# Board1.net
KiCad netlist of a schematic drawn in EAGLE
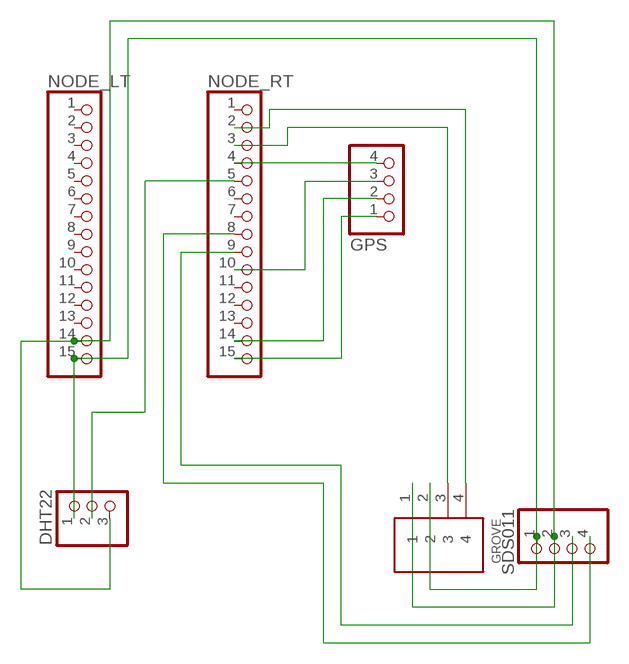
[diagram p0: schematic, sheet 1]

(export (version "E")
  (design (tool "Eeschema 10.0.6"))
  (components
    (comp (ref "DHT22")
      (value "PINHD-1X3")
      (footprint "eagle-import:1X03")
      (libsource (lib "eagle-import") (part "PINHD-1X3"))
    )
    (comp (ref "GPS")
      (value "PINHD-1X4")
      (footprint "eagle-import:1X04")
      (libsource (lib "eagle-import") (part "PINHD-1X4"))
    )
    (comp (ref "GROVE")
      (value "4PIN")
      (footprint "eagle-import:B4B-PH-K-S")
      (libsource (lib "eagle-import") (part "4PIN"))
    )
    (comp (ref "NODE_LT")
      (value "PINHD-1X15")
      (footprint "eagle-import:1X15")
      (libsource (lib "eagle-import") (part "PINHD-1X15"))
    )
    (comp (ref "NODE_RT")
      (value "PINHD-1X15")
      (footprint "eagle-import:1X15")
      (libsource (lib "eagle-import") (part "PINHD-1X15"))
    )
    (comp (ref "SDS011")
      (value "PINHD-1X4")
      (footprint "eagle-import:1X04")
      (libsource (lib "eagle-import") (part "PINHD-1X4"))
    )
  )
  (nets
    (net (code "1") (name "Net-(DHT22-Pad1)") (class "Default")
      (node (ref "DHT22") (pin "1") (pinfunction "1_1") (pintype "passive"))
      (node (ref "GROVE") (pin "2") (pinfunction "2_2") (pintype "bidirectional"))
      (node (ref "NODE_LT") (pin "15") (pinfunction "15_15") (pintype "passive"))
      (node (ref "SDS011") (pin "1") (pinfunction "1_1") (pintype "passive"))
    )
    (net (code "2") (name "Net-(DHT22-Pad2)") (class "Default")
      (node (ref "DHT22") (pin "2") (pinfunction "2_2") (pintype "passive"))
      (node (ref "NODE_RT") (pin "5") (pinfunction "5_5") (pintype "passive"))
    )
    (net (code "3") (name "Net-(DHT22-Pad3)") (class "Default")
      (node (ref "DHT22") (pin "3") (pinfunction "3_3") (pintype "passive"))
      (node (ref "GROVE") (pin "1") (pinfunction "1_1") (pintype "bidirectional"))
      (node (ref "NODE_LT") (pin "14") (pinfunction "14_14") (pintype "passive"))
      (node (ref "SDS011") (pin "2") (pinfunction "2_2") (pintype "passive"))
    )
    (net (code "4") (name "Net-(GPS-Pad1)") (class "Default")
      (node (ref "GPS") (pin "1") (pinfunction "1_1") (pintype "passive"))
      (node (ref "NODE_RT") (pin "15") (pinfunction "15_15") (pintype "passive"))
    )
    (net (code "5") (name "Net-(GPS-Pad2)") (class "Default")
      (node (ref "GPS") (pin "2") (pinfunction "2_2") (pintype "passive"))
      (node (ref "NODE_RT") (pin "14") (pinfunction "14_14") (pintype "passive"))
    )
    (net (code "6") (name "Net-(GPS-Pad3)") (class "Default")
      (node (ref "GPS") (pin "3") (pinfunction "3_3") (pintype "passive"))
      (node (ref "NODE_RT") (pin "10") (pinfunction "10_10") (pintype "passive"))
    )
    (net (code "7") (name "Net-(GPS-Pad4)") (class "Default")
      (node (ref "GPS") (pin "4") (pinfunction "4_4") (pintype "passive"))
      (node (ref "NODE_RT") (pin "4") (pinfunction "4_4") (pintype "passive"))
    )
    (net (code "8") (name "Net-(GROVE-Pad3)") (class "Default")
      (node (ref "GROVE") (pin "3") (pinfunction "3_3") (pintype "bidirectional"))
      (node (ref "NODE_RT") (pin "3") (pinfunction "3_3") (pintype "passive"))
    )
    (net (code "9") (name "Net-(GROVE-Pad4)") (class "Default")
      (node (ref "GROVE") (pin "4") (pinfunction "4_4") (pintype "bidirectional"))
      (node (ref "NODE_RT") (pin "2") (pinfunction "2_2") (pintype "passive"))
    )
    (net (code "10") (name "Net-(NODE_RT-Pad8)") (class "Default")
      (node (ref "NODE_RT") (pin "8") (pinfunction "8_8") (pintype "passive"))
      (node (ref "SDS011") (pin "4") (pinfunction "4_4") (pintype "passive"))
    )
    (net (code "11") (name "Net-(NODE_RT-Pad9)") (class "Default")
      (node (ref "NODE_RT") (pin "9") (pinfunction "9_9") (pintype "passive"))
      (node (ref "SDS011") (pin "3") (pinfunction "3_3") (pintype "passive"))
    )
    (net (code "12") (name "unconnected-(NODE_LT-Pad1)") (class "Default")
      (node (ref "NODE_LT") (pin "1") (pinfunction "1_1") (pintype "passive"))
    )
    (net (code "13") (name "unconnected-(NODE_LT-Pad2)") (class "Default")
      (node (ref "NODE_LT") (pin "2") (pinfunction "2_2") (pintype "passive"))
    )
    (net (code "14") (name "unconnected-(NODE_LT-Pad3)") (class "Default")
      (node (ref "NODE_LT") (pin "3") (pinfunction "3_3") (pintype "passive"))
    )
    (net (code "15") (name "unconnected-(NODE_LT-Pad4)") (class "Default")
      (node (ref "NODE_LT") (pin "4") (pinfunction "4_4") (pintype "passive"))
    )
    (net (code "16") (name "unconnected-(NODE_LT-Pad5)") (class "Default")
      (node (ref "NODE_LT") (pin "5") (pinfunction "5_5") (pintype "passive"))
    )
    (net (code "17") (name "unconnected-(NODE_LT-Pad6)") (class "Default")
      (node (ref "NODE_LT") (pin "6") (pinfunction "6_6") (pintype "passive"))
    )
    (net (code "18") (name "unconnected-(NODE_LT-Pad7)") (class "Default")
      (node (ref "NODE_LT") (pin "7") (pinfunction "7_7") (pintype "passive"))
    )
    (net (code "19") (name "unconnected-(NODE_LT-Pad8)") (class "Default")
      (node (ref "NODE_LT") (pin "8") (pinfunction "8_8") (pintype "passive"))
    )
    (net (code "20") (name "unconnected-(NODE_LT-Pad9)") (class "Default")
      (node (ref "NODE_LT") (pin "9") (pinfunction "9_9") (pintype "passive"))
    )
    (net (code "21") (name "unconnected-(NODE_LT-Pad10)") (class "Default")
      (node (ref "NODE_LT") (pin "10") (pinfunction "10_10") (pintype "passive"))
    )
    (net (code "22") (name "unconnected-(NODE_LT-Pad11)") (class "Default")
      (node (ref "NODE_LT") (pin "11") (pinfunction "11_11") (pintype "passive"))
    )
    (net (code "23") (name "unconnected-(NODE_LT-Pad12)") (class "Default")
      (node (ref "NODE_LT") (pin "12") (pinfunction "12_12") (pintype "passive"))
    )
    (net (code "24") (name "unconnected-(NODE_LT-Pad13)") (class "Default")
      (node (ref "NODE_LT") (pin "13") (pinfunction "13_13") (pintype "passive"))
    )
    (net (code "25") (name "unconnected-(NODE_RT-Pad1)") (class "Default")
      (node (ref "NODE_RT") (pin "1") (pinfunction "1_1") (pintype "passive"))
    )
    (net (code "26") (name "unconnected-(NODE_RT-Pad6)") (class "Default")
      (node (ref "NODE_RT") (pin "6") (pinfunction "6_6") (pintype "passive"))
    )
    (net (code "27") (name "unconnected-(NODE_RT-Pad7)") (class "Default")
      (node (ref "NODE_RT") (pin "7") (pinfunction "7_7") (pintype "passive"))
    )
    (net (code "28") (name "unconnected-(NODE_RT-Pad11)") (class "Default")
      (node (ref "NODE_RT") (pin "11") (pinfunction "11_11") (pintype "passive"))
    )
    (net (code "29") (name "unconnected-(NODE_RT-Pad12)") (class "Default")
      (node (ref "NODE_RT") (pin "12") (pinfunction "12_12") (pintype "passive"))
    )
    (net (code "30") (name "unconnected-(NODE_RT-Pad13)") (class "Default")
      (node (ref "NODE_RT") (pin "13") (pinfunction "13_13") (pintype "passive"))
    )
  )
)
